# ESP8266_Dimmer.net
KiCad netlist of a schematic drawn in EAGLE
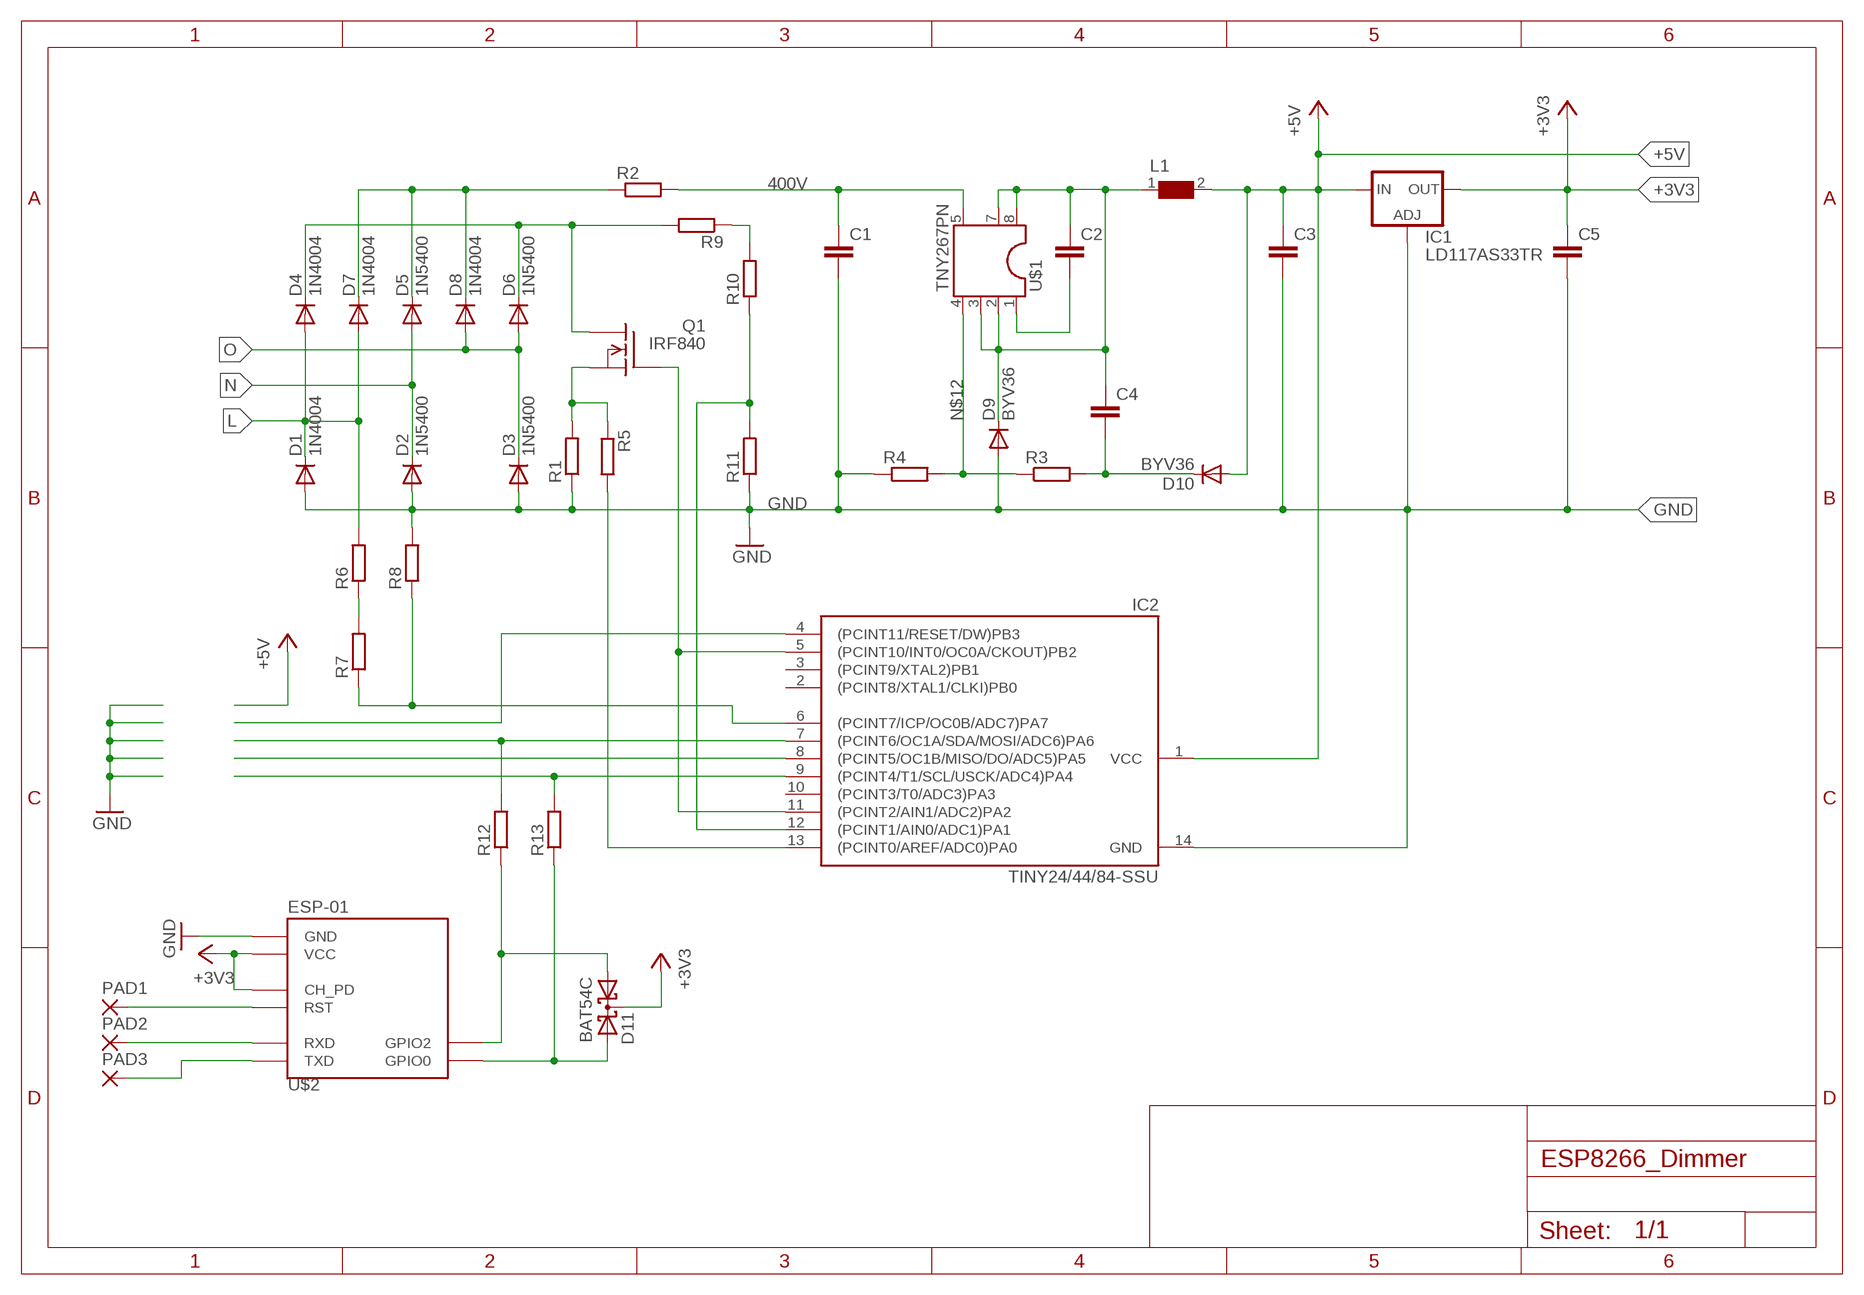
[diagram p0: schematic, sheet 1]

(export (version "E")
  (design (tool "Eeschema 10.0.6"))
  (components
    (comp (ref "C1")
      (value "C-EUC1812")
      (footprint "eagle-import:C1812")
      (libsource (lib "eagle-import") (part "C-EUC1812"))
    )
    (comp (ref "C2")
      (value "C-EUC0805")
      (footprint "eagle-import:C0805")
      (libsource (lib "eagle-import") (part "C-EUC0805"))
    )
    (comp (ref "C3")
      (value "C-EUC0805")
      (footprint "eagle-import:C0805")
      (libsource (lib "eagle-import") (part "C-EUC0805"))
    )
    (comp (ref "C4")
      (value "C-EUC0805")
      (footprint "eagle-import:C0805")
      (libsource (lib "eagle-import") (part "C-EUC0805"))
    )
    (comp (ref "C5")
      (value "C-EUC0805")
      (footprint "eagle-import:C0805")
      (libsource (lib "eagle-import") (part "C-EUC0805"))
    )
    (comp (ref "D1")
      (value "1N4004")
      (footprint "eagle-import:DO41-10")
      (libsource (lib "eagle-import") (part "1N4004"))
    )
    (comp (ref "D2")
      (value "1N5400")
      (footprint "eagle-import:DO201-15")
      (libsource (lib "eagle-import") (part "1N5400"))
    )
    (comp (ref "D3")
      (value "1N5400")
      (footprint "eagle-import:DO201-15")
      (libsource (lib "eagle-import") (part "1N5400"))
    )
    (comp (ref "D4")
      (value "1N4004")
      (footprint "eagle-import:DO41-10")
      (libsource (lib "eagle-import") (part "1N4004"))
    )
    (comp (ref "D5")
      (value "1N5400")
      (footprint "eagle-import:DO201-15")
      (libsource (lib "eagle-import") (part "1N5400"))
    )
    (comp (ref "D6")
      (value "1N5400")
      (footprint "eagle-import:DO201-15")
      (libsource (lib "eagle-import") (part "1N5400"))
    )
    (comp (ref "D7")
      (value "1N4004")
      (footprint "eagle-import:DO41-10")
      (libsource (lib "eagle-import") (part "1N4004"))
    )
    (comp (ref "D8")
      (value "1N4004")
      (footprint "eagle-import:DO41-10")
      (libsource (lib "eagle-import") (part "1N4004"))
    )
    (comp (ref "D9")
      (value "BYV36")
      (footprint "eagle-import:SOD57-10")
      (libsource (lib "eagle-import") (part "BYV36"))
    )
    (comp (ref "D10")
      (value "BYV36")
      (footprint "eagle-import:SOD57-10")
      (libsource (lib "eagle-import") (part "BYV36"))
    )
    (comp (ref "D11")
      (value "BAT54C")
      (footprint "eagle-import:SOT23")
      (libsource (lib "eagle-import") (part "BAT54C"))
    )
    (comp (ref "IC1")
      (value "LD117AS33TR")
      (footprint "eagle-import:SOT223")
      (libsource (lib "eagle-import") (part "LD117A?S33TR"))
    )
    (comp (ref "IC2")
      (value "TINY24/44/84-SSU")
      (footprint "eagle-import:SOIC14")
      (libsource (lib "eagle-import") (part "TINY24/44/84-SSU"))
    )
    (comp (ref "L1")
      (value "WE-FPI")
      (footprint "eagle-import:WE-FPI_744010...")
      (libsource (lib "eagle-import") (part "WE-FPI"))
    )
    (comp (ref "PAD1")
      (value "1,6/0,8")
      (footprint "eagle-import:1,6_0,8")
      (libsource (lib "eagle-import") (part "1,6/0,8"))
    )
    (comp (ref "PAD2")
      (value "1,6/0,8")
      (footprint "eagle-import:1,6_0,8")
      (libsource (lib "eagle-import") (part "1,6/0,8"))
    )
    (comp (ref "PAD3")
      (value "1,6/0,8")
      (footprint "eagle-import:1,6_0,8")
      (libsource (lib "eagle-import") (part "1,6/0,8"))
    )
    (comp (ref "Q1")
      (value "IRF840")
      (footprint "eagle-import:TO220")
      (libsource (lib "eagle-import") (part "IRF840"))
    )
    (comp (ref "R1")
      (value "R-EU_M1206")
      (footprint "eagle-import:M1206")
      (libsource (lib "eagle-import") (part "R-EU_M1206"))
    )
    (comp (ref "R2")
      (value "R-EU_0204/5")
      (footprint "eagle-import:0204_5")
      (libsource (lib "eagle-import") (part "R-EU_0204/5"))
    )
    (comp (ref "R3")
      (value "R-EU_R0805")
      (footprint "eagle-import:R0805")
      (libsource (lib "eagle-import") (part "R-EU_R0805"))
    )
    (comp (ref "R4")
      (value "R-EU_R0805")
      (footprint "eagle-import:R0805")
      (libsource (lib "eagle-import") (part "R-EU_R0805"))
    )
    (comp (ref "R5")
      (value "R-EU_M1206")
      (footprint "eagle-import:M1206")
      (libsource (lib "eagle-import") (part "R-EU_M1206"))
    )
    (comp (ref "R6")
      (value "R-EU_0204/7")
      (footprint "eagle-import:0204_7")
      (libsource (lib "eagle-import") (part "R-EU_0204/7"))
    )
    (comp (ref "R7")
      (value "R-EU_0204/7")
      (footprint "eagle-import:0204_7")
      (libsource (lib "eagle-import") (part "R-EU_0204/7"))
    )
    (comp (ref "R8")
      (value "R-EU_0204/7")
      (footprint "eagle-import:0204_7")
      (libsource (lib "eagle-import") (part "R-EU_0204/7"))
    )
    (comp (ref "R9")
      (value "R-EU_0204/7")
      (footprint "eagle-import:0204_7")
      (libsource (lib "eagle-import") (part "R-EU_0204/7"))
    )
    (comp (ref "R10")
      (value "R-EU_0204/7")
      (footprint "eagle-import:0204_7")
      (libsource (lib "eagle-import") (part "R-EU_0204/7"))
    )
    (comp (ref "R11")
      (value "R-EU_0204/7")
      (footprint "eagle-import:0204_7")
      (libsource (lib "eagle-import") (part "R-EU_0204/7"))
    )
    (comp (ref "R12")
      (value "R-EU_0204/7")
      (footprint "eagle-import:0204_7")
      (libsource (lib "eagle-import") (part "R-EU_0204/7"))
    )
    (comp (ref "R13")
      (value "R-EU_0204/7")
      (footprint "eagle-import:0204_7")
      (libsource (lib "eagle-import") (part "R-EU_0204/7"))
    )
    (comp (ref "U$1")
      (value "TNY267PN")
      (footprint "eagle-import:DIP-8B")
      (libsource (lib "eagle-import") (part "TNY267PN"))
    )
    (comp (ref "U$2")
      (value "ESP-01")
      (footprint "eagle-import:ESP-01")
      (libsource (lib "eagle-import") (part "ESP-01"))
    )
  )
  (nets
    (net (code "1") (name "+3V3") (class "Default")
      (node (ref "C5") (pin "1") (pinfunction "1_1") (pintype "passive"))
      (node (ref "D11") (pin "3") (pinfunction "CC_3") (pintype "passive"))
      (node (ref "IC1") (pin "4") (pinfunction "OUT_4") (pintype "passive"))
      (node (ref "U$2") (pin "CH_PD") (pinfunction "CH_PD_CH_PD") (pintype "bidirectional"))
      (node (ref "U$2") (pin "VCC") (pinfunction "VCC_VCC") (pintype "bidirectional"))
    )
    (net (code "2") (name "+5V") (class "Default")
      (node (ref "C3") (pin "1") (pinfunction "1_1") (pintype "passive"))
      (node (ref "D10") (pin "A") (pinfunction "A_A") (pintype "passive"))
      (node (ref "IC1") (pin "3") (pinfunction "IN_3") (pintype "input"))
      (node (ref "IC2") (pin "1") (pinfunction "VCC_1") (pintype "power_in"))
      (node (ref "L1") (pin "2") (pinfunction "2_2") (pintype "passive"))
    )
    (net (code "3") (name "/400V") (class "Default")
      (node (ref "C1") (pin "1") (pinfunction "1_1") (pintype "passive"))
      (node (ref "R2") (pin "2") (pinfunction "2_2") (pintype "passive"))
      (node (ref "U$1") (pin "5") (pinfunction "D_5") (pintype "passive"))
    )
    (net (code "4") (name "/N$12") (class "Default")
      (node (ref "R3") (pin "1") (pinfunction "1_1") (pintype "passive"))
      (node (ref "R4") (pin "2") (pinfunction "2_2") (pintype "passive"))
      (node (ref "U$1") (pin "4") (pinfunction "EN/UV_4") (pintype "passive"))
    )
    (net (code "5") (name "GND") (class "Default")
      (node (ref "C1") (pin "2") (pinfunction "2_2") (pintype "passive"))
      (node (ref "C3") (pin "2") (pinfunction "2_2") (pintype "passive"))
      (node (ref "C5") (pin "2") (pinfunction "2_2") (pintype "passive"))
      (node (ref "D1") (pin "A") (pinfunction "A_A") (pintype "passive"))
      (node (ref "D2") (pin "A") (pinfunction "A_A") (pintype "passive"))
      (node (ref "D3") (pin "A") (pinfunction "A_A") (pintype "passive"))
      (node (ref "D9") (pin "A") (pinfunction "A_A") (pintype "passive"))
      (node (ref "IC1") (pin "1") (pinfunction "ADJ_1") (pintype "input"))
      (node (ref "IC2") (pin "14") (pinfunction "GND_14") (pintype "power_in"))
      (node (ref "R1") (pin "1") (pinfunction "1_1") (pintype "passive"))
      (node (ref "R11") (pin "1") (pinfunction "1_1") (pintype "passive"))
      (node (ref "R4") (pin "1") (pinfunction "1_1") (pintype "passive"))
      (node (ref "R8") (pin "2") (pinfunction "2_2") (pintype "passive"))
      (node (ref "U$2") (pin "GND") (pinfunction "GND_GND") (pintype "bidirectional"))
    )
    (net (code "6") (name "L") (class "Default")
      (node (ref "D1") (pin "C") (pinfunction "C_C") (pintype "passive"))
      (node (ref "D4") (pin "A") (pinfunction "A_A") (pintype "passive"))
      (node (ref "D7") (pin "A") (pinfunction "A_A") (pintype "passive"))
      (node (ref "R6") (pin "2") (pinfunction "2_2") (pintype "passive"))
    )
    (net (code "7") (name "N") (class "Default")
      (node (ref "D2") (pin "C") (pinfunction "C_C") (pintype "passive"))
      (node (ref "D5") (pin "A") (pinfunction "A_A") (pintype "passive"))
    )
    (net (code "8") (name "Net-(C4-Pad2)") (class "Default")
      (node (ref "C4") (pin "2") (pinfunction "2_2") (pintype "passive"))
      (node (ref "D10") (pin "C") (pinfunction "C_C") (pintype "passive"))
      (node (ref "R3") (pin "2") (pinfunction "2_2") (pintype "passive"))
    )
    (net (code "9") (name "Net-(D5-PadC)") (class "Default")
      (node (ref "D5") (pin "C") (pinfunction "C_C") (pintype "passive"))
      (node (ref "D7") (pin "C") (pinfunction "C_C") (pintype "passive"))
      (node (ref "D8") (pin "C") (pinfunction "C_C") (pintype "passive"))
      (node (ref "R2") (pin "1") (pinfunction "1_1") (pintype "passive"))
    )
    (net (code "10") (name "Net-(D11-A1)") (class "Default")
      (node (ref "D11") (pin "1") (pinfunction "A1_1") (pintype "passive"))
      (node (ref "R12") (pin "1") (pinfunction "1_1") (pintype "passive"))
      (node (ref "U$2") (pin "GPIO2") (pinfunction "GPIO2_GPIO2") (pintype "bidirectional"))
    )
    (net (code "11") (name "Net-(D11-A2)") (class "Default")
      (node (ref "D11") (pin "2") (pinfunction "A2_2") (pintype "passive"))
      (node (ref "R13") (pin "1") (pinfunction "1_1") (pintype "passive"))
      (node (ref "U$2") (pin "GPIO0") (pinfunction "GPIO0_GPIO0") (pintype "bidirectional"))
    )
    (net (code "12") (name "Net-(IC2-(PCINT0{slash}AREF{slash}ADC0)PA0)") (class "Default")
      (node (ref "IC2") (pin "13") (pinfunction "(PCINT0/AREF/ADC0)PA0_13") (pintype "bidirectional"))
      (node (ref "R5") (pin "2") (pinfunction "2_2") (pintype "passive"))
    )
    (net (code "13") (name "Net-(IC2-(PCINT1{slash}AIN0{slash}ADC1)PA1)") (class "Default")
      (node (ref "IC2") (pin "12") (pinfunction "(PCINT1/AIN0/ADC1)PA1_12") (pintype "bidirectional"))
      (node (ref "R10") (pin "1") (pinfunction "1_1") (pintype "passive"))
      (node (ref "R11") (pin "2") (pinfunction "2_2") (pintype "passive"))
    )
    (net (code "14") (name "Net-(IC2-(PCINT4{slash}T1{slash}SCL{slash}USCK{slash}ADC4)PA4)") (class "Default")
      (node (ref "IC2") (pin "9") (pinfunction "(PCINT4/T1/SCL/USCK/ADC4)PA4_9") (pintype "bidirectional"))
      (node (ref "R13") (pin "2") (pinfunction "2_2") (pintype "passive"))
    )
    (net (code "15") (name "Net-(IC2-(PCINT6{slash}OC1A{slash}SDA{slash}MOSI{slash}ADC6)PA6)") (class "Default")
      (node (ref "IC2") (pin "7") (pinfunction "(PCINT6/OC1A/SDA/MOSI/ADC6)PA6_7") (pintype "bidirectional"))
      (node (ref "R12") (pin "2") (pinfunction "2_2") (pintype "passive"))
    )
    (net (code "16") (name "Net-(IC2-(PCINT7{slash}ICP{slash}OC0B{slash}ADC7)PA7)") (class "Default")
      (node (ref "IC2") (pin "6") (pinfunction "(PCINT7/ICP/OC0B/ADC7)PA7_6") (pintype "bidirectional"))
      (node (ref "R7") (pin "1") (pinfunction "1_1") (pintype "passive"))
      (node (ref "R8") (pin "1") (pinfunction "1_1") (pintype "passive"))
    )
    (net (code "17") (name "Net-(IC2-(PCINT10{slash}INT0{slash}OC0A{slash}CKOUT)PB2)") (class "Default")
      (node (ref "IC2") (pin "11") (pinfunction "(PCINT2/AIN1/ADC2)PA2_11") (pintype "bidirectional"))
      (node (ref "IC2") (pin "5") (pinfunction "(PCINT10/INT0/OC0A/CKOUT)PB2_5") (pintype "bidirectional"))
      (node (ref "Q1") (pin "1") (pinfunction "G_1") (pintype "passive"))
    )
    (net (code "18") (name "Net-(PAD1-P)") (class "Default")
      (node (ref "PAD1") (pin "1") (pinfunction "P_1") (pintype "passive"))
      (node (ref "U$2") (pin "RST") (pinfunction "RST_RST") (pintype "bidirectional"))
    )
    (net (code "19") (name "Net-(PAD2-P)") (class "Default")
      (node (ref "PAD2") (pin "1") (pinfunction "P_1") (pintype "passive"))
      (node (ref "U$2") (pin "RX") (pinfunction "RXD_RX") (pintype "bidirectional"))
    )
    (net (code "20") (name "Net-(PAD3-P)") (class "Default")
      (node (ref "PAD3") (pin "1") (pinfunction "P_1") (pintype "passive"))
      (node (ref "U$2") (pin "TX") (pinfunction "TXD_TX") (pintype "bidirectional"))
    )
    (net (code "21") (name "Net-(Q1-D)") (class "Default")
      (node (ref "D4") (pin "C") (pinfunction "C_C") (pintype "passive"))
      (node (ref "D6") (pin "C") (pinfunction "C_C") (pintype "passive"))
      (node (ref "Q1") (pin "2") (pinfunction "D_2") (pintype "passive"))
      (node (ref "R9") (pin "2") (pinfunction "2_2") (pintype "passive"))
    )
    (net (code "22") (name "Net-(Q1-S)") (class "Default")
      (node (ref "Q1") (pin "3") (pinfunction "S_3") (pintype "passive"))
      (node (ref "R1") (pin "2") (pinfunction "2_2") (pintype "passive"))
      (node (ref "R5") (pin "1") (pinfunction "1_1") (pintype "passive"))
    )
    (net (code "23") (name "Net-(R6-Pad1)") (class "Default")
      (node (ref "R6") (pin "1") (pinfunction "1_1") (pintype "passive"))
      (node (ref "R7") (pin "2") (pinfunction "2_2") (pintype "passive"))
    )
    (net (code "24") (name "Net-(R10-Pad2)") (class "Default")
      (node (ref "R10") (pin "2") (pinfunction "2_2") (pintype "passive"))
      (node (ref "R9") (pin "1") (pinfunction "1_1") (pintype "passive"))
    )
    (net (code "25") (name "Net-(U$1-2GND)") (class "Default")
      (node (ref "C2") (pin "1") (pinfunction "1_1") (pintype "passive"))
      (node (ref "C4") (pin "1") (pinfunction "1_1") (pintype "passive"))
      (node (ref "D9") (pin "C") (pinfunction "C_C") (pintype "passive"))
      (node (ref "L1") (pin "1") (pinfunction "1_1") (pintype "passive"))
      (node (ref "U$1") (pin "2") (pinfunction "2GND_2") (pintype "passive"))
      (node (ref "U$1") (pin "3") (pinfunction "3GND_3") (pintype "passive"))
      (node (ref "U$1") (pin "7") (pinfunction "7HV-GND_7") (pintype "passive"))
      (node (ref "U$1") (pin "8") (pinfunction "8HV-GND_8") (pintype "passive"))
    )
    (net (code "26") (name "Net-(U$1-BP)") (class "Default")
      (node (ref "C2") (pin "2") (pinfunction "2_2") (pintype "passive"))
      (node (ref "U$1") (pin "1") (pinfunction "BP_1") (pintype "passive"))
    )
    (net (code "27") (name "O") (class "Default")
      (node (ref "D3") (pin "C") (pinfunction "C_C") (pintype "passive"))
      (node (ref "D6") (pin "A") (pinfunction "A_A") (pintype "passive"))
      (node (ref "D8") (pin "A") (pinfunction "A_A") (pintype "passive"))
    )
    (net (code "28") (name "unconnected-(IC2-(PCINT3{slash}T0{slash}ADC3)PA3-Pad10)") (class "Default")
      (node (ref "IC2") (pin "10") (pinfunction "(PCINT3/T0/ADC3)PA3_10") (pintype "bidirectional"))
    )
    (net (code "29") (name "unconnected-(IC2-(PCINT5{slash}OC1B{slash}MISO{slash}DO{slash}ADC5)PA5-Pad8)") (class "Default")
      (node (ref "IC2") (pin "8") (pinfunction "(PCINT5/OC1B/MISO/DO/ADC5)PA5_8") (pintype "bidirectional"))
    )
    (net (code "30") (name "unconnected-(IC2-(PCINT8{slash}XTAL1{slash}CLKI)PB0-Pad2)") (class "Default")
      (node (ref "IC2") (pin "2") (pinfunction "(PCINT8/XTAL1/CLKI)PB0_2") (pintype "bidirectional"))
    )
    (net (code "31") (name "unconnected-(IC2-(PCINT9{slash}XTAL2)PB1-Pad3)") (class "Default")
      (node (ref "IC2") (pin "3") (pinfunction "(PCINT9/XTAL2)PB1_3") (pintype "bidirectional"))
    )
    (net (code "32") (name "unconnected-(IC2-(PCINT11{slash}RESET{slash}DW)PB3-Pad4)") (class "Default")
      (node (ref "IC2") (pin "4") (pinfunction "(PCINT11/RESET/DW)PB3_4") (pintype "bidirectional"))
    )
  )
)
